# Sheet1.net
KiCad netlist of a schematic drawn in Altium Designer
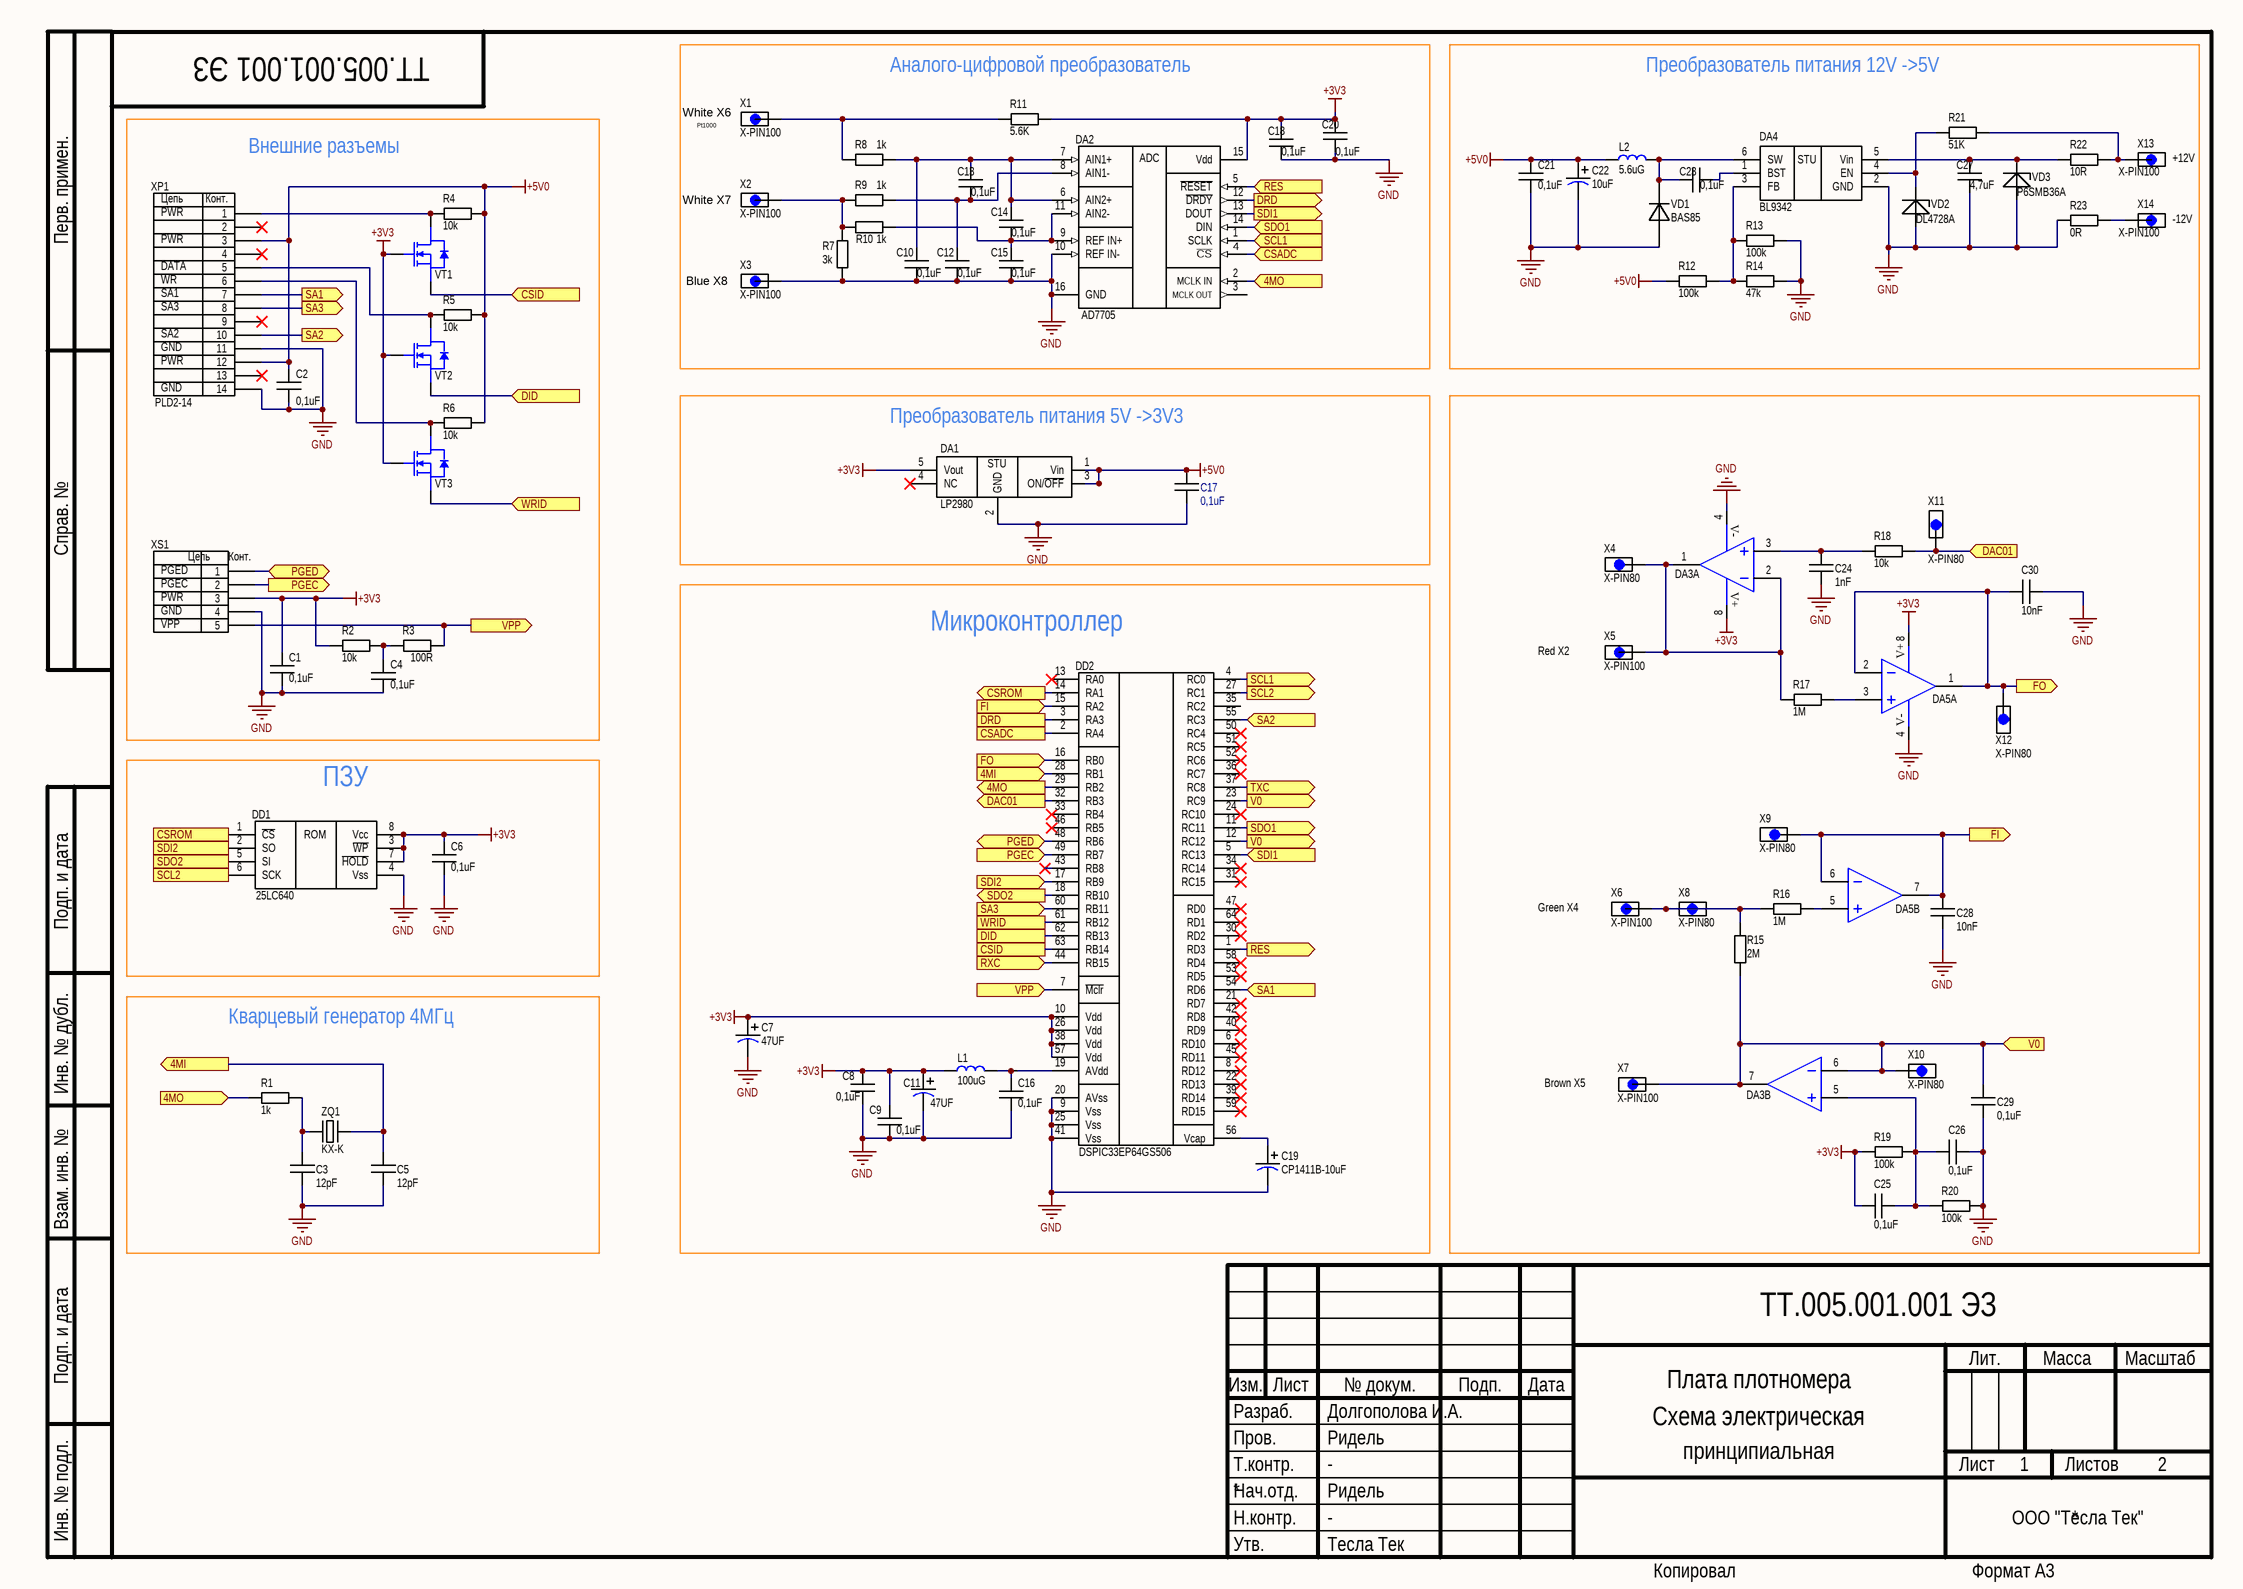
[diagram p0: Sheet1.SCHDOC]

(export (version "E")
  (design (tool "Eeschema 10.0.6"))
  (components
    (comp (ref "C1")
      (value "0,1uF")
      (footprint "0805C")
      (description "C0805 0,1uF")
      (fields
        (field (name "PART NUMBER") "SMD CAP CER 0.1uF ±10% 25V X7R 0805")
        (field (name "ADDED_BY") "ridel_av@teslatec.ru")
      )
      (libsource (lib "81801_1") (part "C0805-0,1uF"))
    )
    (comp (ref "C2")
      (value "0,1uF")
      (footprint "0805C")
      (description "C0805 0,1uF")
      (fields
        (field (name "PART NUMBER") "SMD CAP CER 0.1uF ±10% 25V X7R 0805")
        (field (name "ADDED_BY") "ridel_av@teslatec.ru")
      )
      (libsource (lib "81801_1") (part "C0805-0,1uF"))
    )
    (comp (ref "C3")
      (value "12pF")
      (footprint "0805C")
      (description "C0805 12pF")
      (fields
        (field (name "PART NUMBER") "SMD CAP CER 12pF ±10% 10V X7R 0805")
        (field (name "ADDED_BY") "ridel_av@teslatec.ru")
      )
      (libsource (lib "81801_1") (part "C0805-12pF"))
    )
    (comp (ref "C4")
      (value "0,1uF")
      (footprint "0805C")
      (description "C0805 0,1uF")
      (fields
        (field (name "PART NUMBER") "SMD CAP CER 0.1uF ±10% 25V X7R 0805")
        (field (name "ADDED_BY") "ridel_av@teslatec.ru")
      )
      (libsource (lib "81801_1") (part "C0805-0,1uF"))
    )
    (comp (ref "C5")
      (value "12pF")
      (footprint "0805C")
      (description "C0805 12pF")
      (fields
        (field (name "PART NUMBER") "SMD CAP CER 12pF ±10% 10V X7R 0805")
        (field (name "ADDED_BY") "ridel_av@teslatec.ru")
      )
      (libsource (lib "81801_1") (part "C0805-12pF"))
    )
    (comp (ref "C6")
      (value "0,1uF")
      (footprint "0805C")
      (description "C0805 0,1uF")
      (fields
        (field (name "PART NUMBER") "SMD CAP CER 0.1uF ±10% 25V X7R 0805")
        (field (name "ADDED_BY") "ridel_av@teslatec.ru")
      )
      (libsource (lib "81801_1") (part "C0805-0,1uF"))
    )
    (comp (ref "C7")
      (value "47UF")
      (footprint "B1411_3528")
      (description "CP1411B 47UF 6V3")
      (fields
        (field (name "PART NUMBER") "SMD CAP TANTAL 47uF ±10% 6V3 1411B")
        (field (name "ADDED_BY") "ridel_av@teslatec.ru")
      )
      (libsource (lib "81801_1") (part "CP1411B-47UF"))
    )
    (comp (ref "C8")
      (value "0,1uF")
      (footprint "0805C")
      (description "C0805 0,1uF")
      (fields
        (field (name "PART NUMBER") "SMD CAP CER 0.1uF ±10% 25V X7R 0805")
        (field (name "ADDED_BY") "ridel_av@teslatec.ru")
      )
      (libsource (lib "81801_1") (part "C0805-0,1uF"))
    )
    (comp (ref "C9")
      (value "0,1uF")
      (footprint "0805C")
      (description "C0805 0,1uF")
      (fields
        (field (name "PART NUMBER") "SMD CAP CER 0.1uF ±10% 25V X7R 0805")
        (field (name "ADDED_BY") "ridel_av@teslatec.ru")
      )
      (libsource (lib "81801_1") (part "C0805-0,1uF"))
    )
    (comp (ref "C10")
      (value "0,1uF")
      (footprint "0805C")
      (description "C0805 0,1uF")
      (fields
        (field (name "PART NUMBER") "SMD CAP CER 0.1uF ±10% 25V X7R 0805")
        (field (name "ADDED_BY") "ridel_av@teslatec.ru")
      )
      (libsource (lib "81801_1") (part "C0805-0,1uF"))
    )
    (comp (ref "C11")
      (value "47UF")
      (footprint "B1411_3528")
      (description "CP1411B 47UF 6V3")
      (fields
        (field (name "PART NUMBER") "SMD CAP TANTAL 47uF ±10% 6V3 1411B")
        (field (name "ADDED_BY") "ridel_av@teslatec.ru")
      )
      (libsource (lib "81801_1") (part "CP1411B-47UF"))
    )
    (comp (ref "C12")
      (value "0,1uF")
      (footprint "0805C")
      (description "C0805 0,1uF")
      (fields
        (field (name "PART NUMBER") "SMD CAP CER 0.1uF ±10% 25V X7R 0805")
        (field (name "ADDED_BY") "ridel_av@teslatec.ru")
      )
      (libsource (lib "81801_1") (part "C0805-0,1uF"))
    )
    (comp (ref "C13")
      (value "0,1uF")
      (footprint "0805C")
      (description "C0805 0,1uF")
      (fields
        (field (name "PART NUMBER") "SMD CAP CER 0.1uF ±10% 25V X7R 0805")
        (field (name "ADDED_BY") "ridel_av@teslatec.ru")
      )
      (libsource (lib "81801_1") (part "C0805-0,1uF"))
    )
    (comp (ref "C14")
      (value "0,1uF")
      (footprint "0805C")
      (description "C0805 0,1uF")
      (fields
        (field (name "PART NUMBER") "SMD CAP CER 0.1uF ±10% 25V X7R 0805")
        (field (name "ADDED_BY") "ridel_av@teslatec.ru")
      )
      (libsource (lib "81801_1") (part "C0805-0,1uF"))
    )
    (comp (ref "C15")
      (value "0,1uF")
      (footprint "0805C")
      (description "C0805 0,1uF")
      (fields
        (field (name "PART NUMBER") "SMD CAP CER 0.1uF ±10% 25V X7R 0805")
        (field (name "ADDED_BY") "ridel_av@teslatec.ru")
      )
      (libsource (lib "81801_1") (part "C0805-0,1uF"))
    )
    (comp (ref "C16")
      (value "0,1uF")
      (footprint "0805C")
      (description "C0805 0,1uF")
      (fields
        (field (name "PART NUMBER") "SMD CAP CER 0.1uF ±10% 25V X7R 0805")
        (field (name "ADDED_BY") "ridel_av@teslatec.ru")
      )
      (libsource (lib "81801_1") (part "C0805-0,1uF"))
    )
    (comp (ref "C17")
      (value "0,1uF")
      (footprint "0805C")
      (description "C0805 0,1uF")
      (fields
        (field (name "PART NUMBER") "SMD CAP CER 0.1uF ±10% 25V X7R 0805")
        (field (name "ADDED_BY") "ridel_av@teslatec.ru")
      )
      (libsource (lib "81801_1") (part "C0805-0,1uF"))
    )
    (comp (ref "C18")
      (value "0,1uF")
      (footprint "0805C")
      (description "C0805 0,1uF")
      (fields
        (field (name "PART NUMBER") "SMD CAP CER 0.1uF ±10% 25V X7R 0805")
        (field (name "ADDED_BY") "ridel_av@teslatec.ru")
      )
      (libsource (lib "81801_1") (part "C0805-0,1uF"))
    )
    (comp (ref "C19")
      (value "CP1411B-10uF")
      (footprint "B1411_3528")
      (description "CP1411B 10uF 6V3")
      (fields
        (field (name "PART NUMBER") "SMD CAP TANTAL 10uF ±10% 6V3 1411B")
        (field (name "ADDED_BY") "ridel_av@teslatec.ru")
      )
      (libsource (lib "81801_1") (part "CP1411B-10uF"))
    )
    (comp (ref "C20")
      (value "0,1uF")
      (footprint "0805C")
      (description "C0805 0,1uF")
      (fields
        (field (name "PART NUMBER") "SMD CAP CER 0.1uF ±10% 25V X7R 0805")
        (field (name "ADDED_BY") "ridel_av@teslatec.ru")
      )
      (libsource (lib "81801_1") (part "C0805-0,1uF"))
    )
    (comp (ref "C21")
      (value "0,1uF")
      (footprint "0805C")
      (description "C0805 0,1uF")
      (fields
        (field (name "PART NUMBER") "SMD CAP CER 0.1uF ±10% 25V X7R 0805")
        (field (name "ADDED_BY") "ridel_av@teslatec.ru")
      )
      (libsource (lib "81801_1") (part "C0805-0,1uF"))
    )
    (comp (ref "C22")
      (value "10uF")
      (footprint "B1411_3528")
      (description "CP1411B 10uF 10V")
      (fields
        (field (name "PART NUMBER") "SMD CAP TANTAL 10uF ±10% 10V 1411B")
        (field (name "ADDED_BY") "ridel_av@teslatec.ru")
      )
      (libsource (lib "81801_1") (part "CP1411B-10uF-10V"))
    )
    (comp (ref "C23")
      (value "0,1uF")
      (footprint "0805C")
      (description "C0805 0,1uF")
      (fields
        (field (name "PART NUMBER") "SMD CAP CER 0.1uF ±10% 25V X7R 0805")
        (field (name "ADDED_BY") "ridel_av@teslatec.ru")
      )
      (libsource (lib "81801_1") (part "C0805-0,1uF"))
    )
    (comp (ref "C24")
      (value "1nF")
      (footprint "0805C")
      (description "C0805 1nF")
      (fields
        (field (name "PART NUMBER") "SMD CAP CER 1nF ±10% 50V X7R 0805")
        (field (name "ADDED_BY") "ridel_av@teslatec.ru")
      )
      (libsource (lib "81801_1") (part "C0805-1nF"))
    )
    (comp (ref "C25")
      (value "0,1uF")
      (footprint "0805C")
      (description "C0805 0,1uF")
      (fields
        (field (name "PART NUMBER") "SMD CAP CER 0.1uF ±10% 25V X7R 0805")
        (field (name "ADDED_BY") "ridel_av@teslatec.ru")
      )
      (libsource (lib "81801_1") (part "C0805-0,1uF"))
    )
    (comp (ref "C26")
      (value "0,1uF")
      (footprint "0805C")
      (description "C0805 0,1uF")
      (fields
        (field (name "PART NUMBER") "SMD CAP CER 0.1uF ±10% 25V X7R 0805")
        (field (name "ADDED_BY") "ridel_av@teslatec.ru")
      )
      (libsource (lib "81801_1") (part "C0805-0,1uF"))
    )
    (comp (ref "C27")
      (value "4,7uF")
      (footprint "0805C")
      (description "C0805 4,7uF 50V")
      (fields
        (field (name "PART NUMBER") "SMD CAP CER 4.7uF ±10% 50V X7R 0805")
        (field (name "ADDED_BY") "ridel_av@teslatec.ru")
      )
      (libsource (lib "81801_1") (part "C0805-4,7uF"))
    )
    (comp (ref "C28")
      (value "10nF")
      (footprint "0805C")
      (description "C0805 10nF")
      (fields
        (field (name "PART NUMBER") "SMD CAP CER 10nF ±10% 50V X7R 0805")
        (field (name "ADDED_BY") "ridel_av@teslatec.ru")
      )
      (libsource (lib "81801_1") (part "C0805-10nF"))
    )
    (comp (ref "C29")
      (value "0,1uF")
      (footprint "0805C")
      (description "C0805 0,1uF")
      (fields
        (field (name "PART NUMBER") "SMD CAP CER 0.1uF ±10% 25V X7R 0805")
        (field (name "ADDED_BY") "ridel_av@teslatec.ru")
      )
      (libsource (lib "81801_1") (part "C0805-0,1uF"))
    )
    (comp (ref "C30")
      (value "10nF")
      (footprint "0805C")
      (description "C0805 10nF")
      (fields
        (field (name "PART NUMBER") "SMD CAP CER 10nF ±10% 50V X7R 0805")
        (field (name "ADDED_BY") "ridel_av@teslatec.ru")
      )
      (libsource (lib "81801_1") (part "C0805-10nF"))
    )
    (comp (ref "DA1")
      (value "LP2980")
      (footprint "SOT23-5")
      (description "DA-STU-LP2980, 3.3V, 50mA")
      (fields
        (field (name "PART NUMBER") "LP2980IM5X-3.3/NOPB")
        (field (name "ADDED_BY") "ridel_av@teslatec.ru")
      )
      (libsource (lib "81801_1") (part "DA-STU-LP2980"))
    )
    (comp (ref "DA2")
      (value "AD7705")
      (footprint "SOIC-16")
      (description "DA-ADC-AD7705")
      (fields (field (name "PART NUMBER") "AD7705BR") (field (name "ADDED_BY") "ridel_av@teslatec.ru"))
      (libsource (lib "81801_1") (part "DA-ADC-AD7705SO"))
    )
    (comp (ref "DA3")
      (value "TP6002-SR")
      (footprint "SOIC-8")
      (description "100 mA Output Single-Supply Amplifier")
      (fields (field (name "ADDED_BY") "ridel_av@teslatec.ru"))
      (libsource (lib "81801_1") (part "TP6002-SR"))
    )
    (comp (ref "DA4")
      (value "BL9342")
      (footprint "SOT23-6")
      (description "STU-BL9342, 40V, 600mA")
      (fields (field (name "ADDED_BY") "ridel_av@teslatec.ru"))
      (libsource (lib "81801_1") (part "BL9342"))
    )
    (comp (ref "DA5")
      (value "TP6002-SR")
      (footprint "SOIC-8")
      (description "100 mA Output Single-Supply Amplifier")
      (fields (field (name "ADDED_BY") "ridel_av@teslatec.ru"))
      (libsource (lib "81801_1") (part "TP6002-SR"))
    )
    (comp (ref "DD1")
      (value "25LC640")
      (footprint "SOIC-8")
      (description "25LC640-E/SN, EEPROM, 64Kbit, 2MHz, SPI")
      (fields (field (name "PART NUMBER") "25LC640-E/SN") (field (name "ADDED_BY") "ridel_av@teslatec.ru"))
      (libsource (lib "81801_1") (part "25LC640"))
    )
    (comp (ref "DD2")
      (value "DSPIC33EP64GS506")
      (footprint "TQFP-64")
      (description "DD-CPU-DSPIC33EP64GS506")
      (fields (field (name "ADDED_BY") "ridel_av@teslatec.ru"))
      (libsource (lib "81801_1") (part "DD-CPU-DSPIC33EPXXGS506"))
    )
    (comp (ref "L1")
      (value "100uG")
      (footprint "L1206")
      (description "LQH31CN101K03L, 100 uG, 1206, 10%")
      (fields (field (name "PART NUMBER") "LQH31CN101K03L") (field (name "ADDED_BY") "ridel_av@teslatec.ru"))
      (libsource (lib "81801_1") (part "L1206-100uG"))
    )
    (comp (ref "L2")
      (value "5.6uG")
      (footprint "L1210")
      (description "LQH32MN5R6K23L, 5.6uG, 1210, 10%")
      (fields (field (name "PART NUMBER") "LQH32MN5R6K23L") (field (name "ADDED_BY") "ridel_av@teslatec.ru"))
      (libsource (lib "81801_1") (part "L1210-5.6uG"))
    )
    (comp (ref "R1")
      (value "1k")
      (footprint "R1206")
      (description "R1206 SMD 1k OHM 1% ±100ppm/°C")
      (fields
        (field (name "PART NUMBER") "SMD RES 1k OHM 1% ±100ppm/°C 1206")
        (field (name "ADDED_BY") "ridel_av@teslatec.ru")
      )
      (libsource (lib "81801_1") (part "R1206-1k"))
    )
    (comp (ref "R2")
      (value "10k")
      (footprint "R0805")
      (description "R0805 SMD 10k OHM 1% ±100ppm/°C")
      (fields
        (field (name "PART NUMBER") "SMD RES 10k OHM 1% ±100ppm/°C 0805")
        (field (name "ADDED_BY") "ridel_av@teslatec.ru")
      )
      (libsource (lib "81801_1") (part "R0805-10k"))
    )
    (comp (ref "R3")
      (value "100R")
      (footprint "R1206")
      (description "R1206 100 OHM 1% ±100ppm/°C")
      (fields
        (field (name "PART NUMBER") "SMD RES 100 OHM 1% ±100ppm/°C 1206")
        (field (name "ADDED_BY") "ridel_av@teslatec.ru")
      )
      (libsource (lib "81801_1") (part "R1206-100R"))
    )
    (comp (ref "R4")
      (value "10k")
      (footprint "R0805")
      (description "R0805 SMD 10k OHM 1% ±100ppm/°C")
      (fields
        (field (name "PART NUMBER") "SMD RES 10k OHM 1% ±100ppm/°C 0805")
        (field (name "ADDED_BY") "ridel_av@teslatec.ru")
      )
      (libsource (lib "81801_1") (part "R0805-10k"))
    )
    (comp (ref "R5")
      (value "10k")
      (footprint "R0805")
      (description "R0805 SMD 10k OHM 1% ±100ppm/°C")
      (fields
        (field (name "PART NUMBER") "SMD RES 10k OHM 1% ±100ppm/°C 0805")
        (field (name "ADDED_BY") "ridel_av@teslatec.ru")
      )
      (libsource (lib "81801_1") (part "R0805-10k"))
    )
    (comp (ref "R6")
      (value "10k")
      (footprint "R0805")
      (description "R0805 SMD 10k OHM 1% ±100ppm/°C")
      (fields
        (field (name "PART NUMBER") "SMD RES 10k OHM 1% ±100ppm/°C 0805")
        (field (name "ADDED_BY") "ridel_av@teslatec.ru")
      )
      (libsource (lib "81801_1") (part "R0805-10k"))
    )
    (comp (ref "R7")
      (value "3k")
      (footprint "R1206")
      (description "R1206 SMD 3k OHM 1% ±100ppm/°C")
      (fields
        (field (name "PART NUMBER") "SMD RES 1k OHM 1% ±100ppm/°C 1206")
        (field (name "ADDED_BY") "ridel_av@teslatec.ru")
      )
      (libsource (lib "81801_1") (part "R1206-3k"))
    )
    (comp (ref "R8")
      (value "1k")
      (footprint "R1206")
      (description "R1206 SMD 1k OHM 1% ±100ppm/°C")
      (fields
        (field (name "PART NUMBER") "SMD RES 1k OHM 1% ±100ppm/°C 1206")
        (field (name "ADDED_BY") "ridel_av@teslatec.ru")
      )
      (libsource (lib "81801_1") (part "R1206-1k"))
    )
    (comp (ref "R9")
      (value "1k")
      (footprint "R1206")
      (description "R1206 SMD 1k OHM 1% ±100ppm/°C")
      (fields
        (field (name "PART NUMBER") "SMD RES 1k OHM 1% ±100ppm/°C 1206")
        (field (name "ADDED_BY") "ridel_av@teslatec.ru")
      )
      (libsource (lib "81801_1") (part "R1206-1k"))
    )
    (comp (ref "R10")
      (value "1k")
      (footprint "R1206")
      (description "R1206 SMD 1k OHM 1% ±100ppm/°C")
      (fields
        (field (name "PART NUMBER") "SMD RES 1k OHM 1% ±100ppm/°C 1206")
        (field (name "ADDED_BY") "ridel_av@teslatec.ru")
      )
      (libsource (lib "81801_1") (part "R1206-1k"))
    )
    (comp (ref "R11")
      (value "5.6K")
      (footprint "R1206")
      (description "R1206 5.6k OHM 1% ±100ppm/°C")
      (fields
        (field (name "PART NUMBER") "SMD RES 5.6k OHM 1% ±100ppm/°C 1206")
        (field (name "ADDED_BY") "ridel_av@teslatec.ru")
      )
      (libsource (lib "81801_1") (part "R1206-5.6K"))
    )
    (comp (ref "R12")
      (value "100k")
      (footprint "R1206")
      (description "R1206 100k OHM 1% ±100ppm/°C")
      (fields
        (field (name "PART NUMBER") "SMD RES 100k OHM 1% ±100ppm/°C 1206")
        (field (name "ADDED_BY") "ridel_av@teslatec.ru")
      )
      (libsource (lib "81801_1") (part "R1206-100k"))
    )
    (comp (ref "R13")
      (value "100k")
      (footprint "R1206")
      (description "R1206 100k OHM 1% ±100ppm/°C")
      (fields
        (field (name "PART NUMBER") "SMD RES 100k OHM 1% ±100ppm/°C 1206")
        (field (name "ADDED_BY") "ridel_av@teslatec.ru")
      )
      (libsource (lib "81801_1") (part "R1206-100k"))
    )
    (comp (ref "R14")
      (value "47k")
      (footprint "R1206")
      (description "R1206 47k OHM 1% ±100ppm/°C")
      (fields
        (field (name "PART NUMBER") "SMD RES 47k OHM 1% ±100ppm/°C 1206")
        (field (name "ADDED_BY") "ridel_av@teslatec.ru")
      )
      (libsource (lib "81801_1") (part "R1206-47k"))
    )
    (comp (ref "R15")
      (value "2M")
      (footprint "R1206")
      (description "R1206 2M OHM 1% ±100ppm/°C")
      (fields
        (field (name "PART NUMBER") "SMD RES 2M OHM 1% ±100ppm/°C 1206")
        (field (name "ADDED_BY") "ridel_av@teslatec.ru")
      )
      (libsource (lib "81801_1") (part "R1206-2M"))
    )
    (comp (ref "R16")
      (value "1M")
      (footprint "R1206")
      (description "R1206 1M OHM 1% ±100ppm/°C")
      (fields
        (field (name "PART NUMBER") "SMD RES 1M OHM 1% ±100ppm/°C 1206")
        (field (name "ADDED_BY") "ridel_av@teslatec.ru")
      )
      (libsource (lib "81801_1") (part "R1206-1M"))
    )
    (comp (ref "R17")
      (value "1M")
      (footprint "R1206")
      (description "R1206 1M OHM 1% ±100ppm/°C")
      (fields
        (field (name "PART NUMBER") "SMD RES 1M OHM 1% ±100ppm/°C 1206")
        (field (name "ADDED_BY") "ridel_av@teslatec.ru")
      )
      (libsource (lib "81801_1") (part "R1206-1M"))
    )
    (comp (ref "R18")
      (value "10k")
      (footprint "R0805")
      (description "R0805 SMD 10k OHM 1% ±100ppm/°C")
      (fields
        (field (name "PART NUMBER") "SMD RES 10k OHM 1% ±100ppm/°C 0805")
        (field (name "ADDED_BY") "ridel_av@teslatec.ru")
      )
      (libsource (lib "81801_1") (part "R0805-10k"))
    )
    (comp (ref "R19")
      (value "100k")
      (footprint "R1206")
      (description "R1206 100k OHM 1% ±100ppm/°C")
      (fields
        (field (name "PART NUMBER") "SMD RES 100k OHM 1% ±100ppm/°C 1206")
        (field (name "ADDED_BY") "ridel_av@teslatec.ru")
      )
      (libsource (lib "81801_1") (part "R1206-100k"))
    )
    (comp (ref "R20")
      (value "100k")
      (footprint "R1206")
      (description "R1206 100k OHM 1% ±100ppm/°C")
      (fields
        (field (name "PART NUMBER") "SMD RES 100k OHM 1% ±100ppm/°C 1206")
        (field (name "ADDED_BY") "ridel_av@teslatec.ru")
      )
      (libsource (lib "81801_1") (part "R1206-100k"))
    )
    (comp (ref "R21")
      (value "51K")
      (footprint "R1206")
      (description "R1206 51K OHM 1% ±100ppm/°C")
      (fields
        (field (name "PART NUMBER") "SMD RES 51K OHM 1% ±100ppm/°C 1206")
        (field (name "ADDED_BY") "ridel_av@teslatec.ru")
      )
      (libsource (lib "81801_1") (part "R1206-51K"))
    )
    (comp (ref "R22")
      (value "10R")
      (footprint "R1206")
      (description "R1206 10 OHM 1% ±100ppm/°C")
      (fields
        (field (name "PART NUMBER") "SMD RES 10 OHM 1% ±100ppm/°C 1206")
        (field (name "ADDED_BY") "ridel_av@teslatec.ru")
      )
      (libsource (lib "81801_1") (part "R1206-10R"))
    )
    (comp (ref "R23")
      (value "0R")
      (footprint "R1206")
      (description "R1206-0R")
      (fields
        (field (name "PART NUMBER") "SMD RES 0 OHM 1% ±100ppm/°C 1206")
        (field (name "ADDED_BY") "ridel_av@teslatec.ru")
      )
      (libsource (lib "81801_1") (part "R1206-0R"))
    )
    (comp (ref "VD1")
      (value "BAS85")
      (footprint "SOD-80 MiniMELF")
      (description "BAS85 30В 0.2А")
      (fields (field (name "ADDED_BY") "ridel_av@teslatec.ru"))
      (libsource (lib "81801_1") (part "BAS85"))
    )
    (comp (ref "VD2")
      (value "DL4728A")
      (footprint "DO-213AB")
      (description "DL4728A, 3V3")
      (fields (field (name "ADDED_BY") "ridel_av@teslatec.ru"))
      (libsource (lib "81801_1") (part "DL4728A"))
    )
    (comp (ref "VD3")
      (value "P6SMB36A")
      (footprint "SMB(DO-214AA )")
      (description "P6SMB36A, 49.9V")
      (fields (field (name "ADDED_BY") "ridel_av@teslatec.ru"))
      (libsource (lib "81801_1") (part "P6SMB36A"))
    )
    (comp (ref "VT1")
      (value "VT-MOSFET-N-SOT23")
      (footprint "SOT-23-3")
      (description "2N7002, MOSFET-N, 60V, 115mA, SOT-23-3")
      (fields (field (name "PART NUMBER") "2N7002") (field (name "ADDED_BY") "ridel_av@teslatec.ru"))
      (libsource (lib "81801_1") (part "2N7002"))
    )
    (comp (ref "VT2")
      (value "VT-MOSFET-N-SOT23")
      (footprint "SOT-23-3")
      (description "2N7002, MOSFET-N, 60V, 115mA, SOT-23-3")
      (fields (field (name "PART NUMBER") "2N7002") (field (name "ADDED_BY") "ridel_av@teslatec.ru"))
      (libsource (lib "81801_1") (part "2N7002"))
    )
    (comp (ref "VT3")
      (value "VT-MOSFET-N-SOT23")
      (footprint "SOT-23-3")
      (description "2N7002, MOSFET-N, 60V, 115mA, SOT-23-3")
      (fields (field (name "PART NUMBER") "2N7002") (field (name "ADDED_BY") "ridel_av@teslatec.ru"))
      (libsource (lib "81801_1") (part "2N7002"))
    )
    (comp (ref "X1")
      (value "X-PIN100")
      (footprint "Xpin100")
      (fields (field (name "ADDED_BY") "ridel_av@teslatec.ru"))
      (libsource (lib "81801_1") (part "X-PIN100"))
    )
    (comp (ref "X2")
      (value "X-PIN100")
      (footprint "Xpin100")
      (fields (field (name "ADDED_BY") "ridel_av@teslatec.ru"))
      (libsource (lib "81801_1") (part "X-PIN100"))
    )
    (comp (ref "X3")
      (value "X-PIN100")
      (footprint "Xpin100")
      (fields (field (name "ADDED_BY") "ridel_av@teslatec.ru"))
      (libsource (lib "81801_1") (part "X-PIN100"))
    )
    (comp (ref "X4")
      (value "X-PIN80")
      (footprint "Xpin80")
      (fields (field (name "ADDED_BY") "ridel_av@teslatec.ru"))
      (libsource (lib "81801_1") (part "X-PIN80"))
    )
    (comp (ref "X5")
      (value "X-PIN100")
      (footprint "Xpin100")
      (fields (field (name "ADDED_BY") "ridel_av@teslatec.ru"))
      (libsource (lib "81801_1") (part "X-PIN100"))
    )
    (comp (ref "X6")
      (value "X-PIN100")
      (footprint "Xpin100")
      (fields (field (name "ADDED_BY") "ridel_av@teslatec.ru"))
      (libsource (lib "81801_1") (part "X-PIN100"))
    )
    (comp (ref "X7")
      (value "X-PIN100")
      (footprint "Xpin100")
      (fields (field (name "ADDED_BY") "ridel_av@teslatec.ru"))
      (libsource (lib "81801_1") (part "X-PIN100"))
    )
    (comp (ref "X8")
      (value "X-PIN80")
      (footprint "Xpin80")
      (fields (field (name "ADDED_BY") "ridel_av@teslatec.ru"))
      (libsource (lib "81801_1") (part "X-PIN80"))
    )
    (comp (ref "X9")
      (value "X-PIN80")
      (footprint "Xpin80")
      (fields (field (name "ADDED_BY") "ridel_av@teslatec.ru"))
      (libsource (lib "81801_1") (part "X-PIN80"))
    )
    (comp (ref "X10")
      (value "X-PIN80")
      (footprint "Xpin80")
      (fields (field (name "ADDED_BY") "ridel_av@teslatec.ru"))
      (libsource (lib "81801_1") (part "X-PIN80"))
    )
    (comp (ref "X11")
      (value "X-PIN80")
      (footprint "Xpin80")
      (fields (field (name "ADDED_BY") "ridel_av@teslatec.ru"))
      (libsource (lib "81801_1") (part "X-PIN80"))
    )
    (comp (ref "X12")
      (value "X-PIN80")
      (footprint "Xpin80")
      (fields (field (name "ADDED_BY") "ridel_av@teslatec.ru"))
      (libsource (lib "81801_1") (part "X-PIN80"))
    )
    (comp (ref "X13")
      (value "X-PIN100")
      (footprint "Xpin100")
      (fields (field (name "ADDED_BY") "ridel_av@teslatec.ru"))
      (libsource (lib "81801_1") (part "X-PIN100"))
    )
    (comp (ref "X14")
      (value "X-PIN100")
      (footprint "Xpin100")
      (fields (field (name "ADDED_BY") "ridel_av@teslatec.ru"))
      (libsource (lib "81801_1") (part "X-PIN100"))
    )
    (comp (ref "XP1")
      (value "PLD2-14")
      (footprint "PLD-14- 2.0mm")
      (fields
        (field (name "PART NUMBER") "DS1025-05-2X7P8BV1-B")
        (field (name "ADDED_BY") "ridel_av@teslatec.ru")
      )
      (libsource (lib "81801_1") (part "PLD2-14"))
    )
    (comp (ref "XS1")
      (value "PBS2-5")
      (footprint "PBS-5")
      (fields (field (name "PART NUMBER") "C6801-05ASGL00R") (field (name "ADDED_BY") "ridel_av@teslatec.ru"))
      (libsource (lib "81801_1") (part "PBS2-5"))
    )
    (comp (ref "ZQ1")
      (value "KX-K")
      (footprint "HC¦49US")
      (description "KX-K 4MHz HC/49US")
      (fields
        (field (name "PART NUMBER") "ABLS-4.000MHZ-K4T")
        (field (name "ADDED_BY") "ridel_av@teslatec.ru")
      )
      (libsource (lib "81801_1") (part "ABLS-4.000MHZ-K4T"))
    )
  )
  (nets
    (net (code "1") (name "+3V3") (class "Default")
      (node (ref "C1") (pin "1") (pinfunction "1_1") (pintype "passive"))
      (node (ref "C11") (pin "1") (pinfunction "1_1") (pintype "passive"))
      (node (ref "C18") (pin "2") (pinfunction "2_2") (pintype "passive"))
      (node (ref "C20") (pin "1") (pinfunction "1_1") (pintype "passive"))
      (node (ref "C25") (pin "1") (pinfunction "1_1") (pintype "passive"))
      (node (ref "C6") (pin "2") (pinfunction "2_2") (pintype "passive"))
      (node (ref "C7") (pin "1") (pinfunction "1_1") (pintype "passive"))
      (node (ref "C8") (pin "1") (pinfunction "1_1") (pintype "passive"))
      (node (ref "C9") (pin "1") (pinfunction "1_1") (pintype "passive"))
      (node (ref "DA1") (pin "5") (pinfunction "Vout_5") (pintype "passive"))
      (node (ref "DA2") (pin "15") (pinfunction "Vdd_15") (pintype "power_in"))
      (node (ref "DA3") (pin "8") (pinfunction "8_8") (pintype "passive"))
      (node (ref "DA5") (pin "8") (pinfunction "8_8") (pintype "passive"))
      (node (ref "DD1") (pin "3") (pinfunction "~{WP}_3") (pintype "passive"))
      (node (ref "DD1") (pin "7") (pinfunction "~{HOLD}_7") (pintype "passive"))
      (node (ref "DD1") (pin "8") (pinfunction "Vcc_8") (pintype "passive"))
      (node (ref "DD2") (pin "10") (pinfunction "Vdd_10") (pintype "passive"))
      (node (ref "DD2") (pin "26") (pinfunction "Vdd_26") (pintype "passive"))
      (node (ref "DD2") (pin "38") (pinfunction "Vdd_38") (pintype "passive"))
      (node (ref "DD2") (pin "57") (pinfunction "Vdd_57") (pintype "passive"))
      (node (ref "L1") (pin "1") (pinfunction "1_1") (pintype "passive"))
      (node (ref "R11") (pin "2") (pinfunction "2_2") (pintype "passive"))
      (node (ref "R19") (pin "1") (pinfunction "1_1") (pintype "passive"))
      (node (ref "R2") (pin "1") (pinfunction "1_1") (pintype "passive"))
      (node (ref "VT1") (pin "1") (pinfunction "1_1") (pintype "passive"))
      (node (ref "VT2") (pin "1") (pinfunction "1_1") (pintype "passive"))
      (node (ref "VT3") (pin "1") (pinfunction "1_1") (pintype "passive"))
      (node (ref "XS1") (pin "3") (pinfunction "3_3") (pintype "passive"))
    )
    (net (code "2") (name "+5V0") (class "Default")
      (node (ref "C17") (pin "1") (pinfunction "1_1") (pintype "passive"))
      (node (ref "C2") (pin "1") (pinfunction "1_1") (pintype "passive"))
      (node (ref "C21") (pin "1") (pinfunction "1_1") (pintype "passive"))
      (node (ref "C22") (pin "1") (pinfunction "1_1") (pintype "passive"))
      (node (ref "DA1") (pin "1") (pinfunction "Vin_1") (pintype "passive"))
      (node (ref "DA1") (pin "3") (pinfunction "ON/~{OFF}_3") (pintype "passive"))
      (node (ref "L2") (pin "1") (pinfunction "1_1") (pintype "passive"))
      (node (ref "R12") (pin "1") (pinfunction "1_1") (pintype "passive"))
      (node (ref "R4") (pin "2") (pinfunction "2_2") (pintype "passive"))
      (node (ref "R5") (pin "2") (pinfunction "2_2") (pintype "passive"))
      (node (ref "R6") (pin "2") (pinfunction "2_2") (pintype "passive"))
      (node (ref "XP1") (pin "12") (pinfunction "12_12") (pintype "passive"))
      (node (ref "XP1") (pin "3") (pinfunction "3_3") (pintype "passive"))
    )
    (net (code "3") (name "/4MI") (class "Default")
      (node (ref "C5") (pin "1") (pinfunction "1_1") (pintype "passive"))
      (node (ref "DD2") (pin "28") (pinfunction "RB1_28") (pintype "passive"))
      (node (ref "ZQ1") (pin "2") (pinfunction "OSC2_2") (pintype "passive"))
    )
    (net (code "4") (name "/4MO") (class "Default")
      (node (ref "DA2") (pin "2") (pinfunction "MCLK_IN_2") (pintype "input"))
      (node (ref "DD2") (pin "29") (pinfunction "RB2_29") (pintype "passive"))
      (node (ref "R1") (pin "1") (pinfunction "1_1") (pintype "passive"))
    )
    (net (code "5") (name "/CSADC") (class "Default")
      (node (ref "DA2") (pin "4") (pinfunction "~{CS}_4") (pintype "input"))
      (node (ref "DD2") (pin "2") (pinfunction "RA4_2") (pintype "passive"))
    )
    (net (code "6") (name "/CSID") (class "Default")
      (node (ref "DD2") (pin "63") (pinfunction "RB14_63") (pintype "passive"))
      (node (ref "VT1") (pin "2") (pinfunction "2_2") (pintype "passive"))
    )
    (net (code "7") (name "/CSROM") (class "Default")
      (node (ref "DD1") (pin "1") (pinfunction "~{CS}_1") (pintype "passive"))
      (node (ref "DD2") (pin "14") (pinfunction "RA1_14") (pintype "passive"))
    )
    (net (code "8") (name "/DAC01") (class "Default")
      (node (ref "DD2") (pin "32") (pinfunction "RB3_32") (pintype "passive"))
      (node (ref "R18") (pin "2") (pinfunction "2_2") (pintype "passive"))
      (node (ref "X11") (pin "1") (pinfunction "Contact0_1") (pintype "passive"))
    )
    (net (code "9") (name "/DID") (class "Default")
      (node (ref "DD2") (pin "62") (pinfunction "RB13_62") (pintype "passive"))
      (node (ref "VT2") (pin "2") (pinfunction "2_2") (pintype "passive"))
    )
    (net (code "10") (name "/DRD") (class "Default")
      (node (ref "DA2") (pin "12") (pinfunction "~{DRDY}_12") (pintype "output"))
      (node (ref "DD2") (pin "3") (pinfunction "RA3_3") (pintype "passive"))
    )
    (net (code "11") (name "/FI") (class "Default")
      (node (ref "C28") (pin "1") (pinfunction "1_1") (pintype "passive"))
      (node (ref "DA5") (pin "6") (pinfunction "6_6") (pintype "passive"))
      (node (ref "DA5") (pin "7") (pinfunction "7_7") (pintype "passive"))
      (node (ref "DD2") (pin "15") (pinfunction "RA2_15") (pintype "passive"))
      (node (ref "X9") (pin "1") (pinfunction "Contact0_1") (pintype "passive"))
    )
    (net (code "12") (name "/FO") (class "Default")
      (node (ref "C30") (pin "1") (pinfunction "1_1") (pintype "passive"))
      (node (ref "DA5") (pin "1") (pinfunction "1_1") (pintype "passive"))
      (node (ref "DA5") (pin "2") (pinfunction "2_2") (pintype "passive"))
      (node (ref "DD2") (pin "16") (pinfunction "RB0_16") (pintype "passive"))
      (node (ref "X12") (pin "1") (pinfunction "Contact0_1") (pintype "passive"))
    )
    (net (code "13") (name "/PGEC") (class "Default")
      (node (ref "DD2") (pin "49") (pinfunction "RB7_49") (pintype "passive"))
      (node (ref "XS1") (pin "2") (pinfunction "2_2") (pintype "passive"))
    )
    (net (code "14") (name "/PGED") (class "Default")
      (node (ref "DD2") (pin "48") (pinfunction "RB6_48") (pintype "passive"))
      (node (ref "XS1") (pin "1") (pinfunction "1_1") (pintype "passive"))
    )
    (net (code "15") (name "/RES") (class "Default")
      (node (ref "DA2") (pin "5") (pinfunction "~{RESET}_5") (pintype "input"))
      (node (ref "DD2") (pin "1") (pinfunction "RD3_1") (pintype "passive"))
    )
    (net (code "16") (name "/RXC") (class "Default")
      (node (ref "DD2") (pin "44") (pinfunction "RB15_44") (pintype "passive"))
    )
    (net (code "17") (name "/SA1") (class "Default")
      (node (ref "DD2") (pin "54") (pinfunction "RD6_54") (pintype "passive"))
      (node (ref "XP1") (pin "7") (pinfunction "7_7") (pintype "passive"))
    )
    (net (code "18") (name "/SA2") (class "Default")
      (node (ref "DD2") (pin "55") (pinfunction "RC3_55") (pintype "passive"))
      (node (ref "XP1") (pin "10") (pinfunction "10_10") (pintype "passive"))
    )
    (net (code "19") (name "/SA3") (class "Default")
      (node (ref "DD2") (pin "60") (pinfunction "RB11_60") (pintype "passive"))
      (node (ref "XP1") (pin "8") (pinfunction "8_8") (pintype "passive"))
    )
    (net (code "20") (name "/SCL1") (class "Default")
      (node (ref "DA2") (pin "1") (pinfunction "SCLK_1") (pintype "input"))
      (node (ref "DD2") (pin "4") (pinfunction "RC0_4") (pintype "passive"))
    )
    (net (code "21") (name "/SCL2") (class "Default")
      (node (ref "DD1") (pin "6") (pinfunction "SCK_6") (pintype "passive"))
      (node (ref "DD2") (pin "27") (pinfunction "RC1_27") (pintype "passive"))
    )
    (net (code "22") (name "/SDI1") (class "Default")
      (node (ref "DA2") (pin "13") (pinfunction "DOUT_13") (pintype "output"))
      (node (ref "DD2") (pin "5") (pinfunction "RC13_5") (pintype "passive"))
    )
    (net (code "23") (name "/SDI2") (class "Default")
      (node (ref "DD1") (pin "2") (pinfunction "SO_2") (pintype "passive"))
      (node (ref "DD2") (pin "17") (pinfunction "RB9_17") (pintype "passive"))
    )
    (net (code "24") (name "/SDO1") (class "Default")
      (node (ref "DA2") (pin "14") (pinfunction "DIN_14") (pintype "input"))
      (node (ref "DD2") (pin "11") (pinfunction "RC11_11") (pintype "passive"))
    )
    (net (code "25") (name "/SDO2") (class "Default")
      (node (ref "DD1") (pin "5") (pinfunction "SI_5") (pintype "passive"))
      (node (ref "DD2") (pin "18") (pinfunction "RB10_18") (pintype "passive"))
    )
    (net (code "26") (name "/TXC") (class "Default")
      (node (ref "DD2") (pin "37") (pinfunction "RC8_37") (pintype "passive"))
    )
    (net (code "27") (name "/V0") (class "Default")
      (node (ref "C29") (pin "1") (pinfunction "1_1") (pintype "passive"))
      (node (ref "DA3") (pin "6") (pinfunction "6_6") (pintype "passive"))
      (node (ref "DA3") (pin "7") (pinfunction "7_7") (pintype "passive"))
      (node (ref "DD2") (pin "12") (pinfunction "RC12_12") (pintype "passive"))
      (node (ref "DD2") (pin "23") (pinfunction "RC9_23") (pintype "passive"))
      (node (ref "R15") (pin "1") (pinfunction "1_1") (pintype "passive"))
      (node (ref "X10") (pin "1") (pinfunction "Contact0_1") (pintype "passive"))
      (node (ref "X7") (pin "1") (pintype "passive"))
    )
    (net (code "28") (name "/VPP") (class "Default")
      (node (ref "DD2") (pin "7") (pinfunction "~{Mclr}_7") (pintype "passive"))
      (node (ref "R3") (pin "2") (pinfunction "2_2") (pintype "passive"))
      (node (ref "XS1") (pin "5") (pinfunction "5_5") (pintype "passive"))
    )
    (net (code "29") (name "/WRID") (class "Default")
      (node (ref "DD2") (pin "61") (pinfunction "RB12_61") (pintype "passive"))
      (node (ref "VT3") (pin "2") (pinfunction "2_2") (pintype "passive"))
    )
    (net (code "30") (name "GND") (class "Default")
      (node (ref "C1") (pin "2") (pinfunction "2_2") (pintype "passive"))
      (node (ref "C10") (pin "2") (pinfunction "2_2") (pintype "passive"))
      (node (ref "C11") (pin "2") (pinfunction "2_2") (pintype "passive"))
      (node (ref "C12") (pin "2") (pinfunction "2_2") (pintype "passive"))
      (node (ref "C15") (pin "2") (pinfunction "2_2") (pintype "passive"))
      (node (ref "C16") (pin "2") (pinfunction "2_2") (pintype "passive"))
      (node (ref "C17") (pin "2") (pinfunction "2_2") (pintype "passive"))
      (node (ref "C18") (pin "1") (pinfunction "1_1") (pintype "passive"))
      (node (ref "C19") (pin "2") (pinfunction "2_2") (pintype "passive"))
      (node (ref "C2") (pin "2") (pinfunction "2_2") (pintype "passive"))
      (node (ref "C20") (pin "2") (pinfunction "2_2") (pintype "passive"))
      (node (ref "C21") (pin "2") (pinfunction "2_2") (pintype "passive"))
      (node (ref "C22") (pin "2") (pinfunction "2_2") (pintype "passive"))
      (node (ref "C24") (pin "1") (pinfunction "1_1") (pintype "passive"))
      (node (ref "C26") (pin "2") (pinfunction "2_2") (pintype "passive"))
      (node (ref "C27") (pin "2") (pinfunction "2_2") (pintype "passive"))
      (node (ref "C28") (pin "2") (pinfunction "2_2") (pintype "passive"))
      (node (ref "C29") (pin "2") (pinfunction "2_2") (pintype "passive"))
      (node (ref "C3") (pin "2") (pinfunction "2_2") (pintype "passive"))
      (node (ref "C30") (pin "2") (pinfunction "2_2") (pintype "passive"))
      (node (ref "C4") (pin "2") (pinfunction "2_2") (pintype "passive"))
      (node (ref "C5") (pin "2") (pinfunction "2_2") (pintype "passive"))
      (node (ref "C6") (pin "1") (pinfunction "1_1") (pintype "passive"))
      (node (ref "C7") (pin "2") (pinfunction "2_2") (pintype "passive"))
      (node (ref "C8") (pin "2") (pinfunction "2_2") (pintype "passive"))
      (node (ref "C9") (pin "2") (pinfunction "2_2") (pintype "passive"))
      (node (ref "DA1") (pin "2") (pinfunction "GND_2") (pintype "passive"))
      (node (ref "DA2") (pin "10") (pinfunction "REF_IN-_10") (pintype "input"))
      (node (ref "DA2") (pin "16") (pinfunction "GND_16") (pintype "power_in"))
      (node (ref "DA3") (pin "4") (pinfunction "4_4") (pintype "passive"))
      (node (ref "DA4") (pin "2") (pinfunction "GND_2") (pintype "passive"))
      (node (ref "DA5") (pin "4") (pinfunction "4_4") (pintype "passive"))
      (node (ref "DD1") (pin "4") (pinfunction "Vss_4") (pintype "passive"))
      (node (ref "DD2") (pin "20") (pinfunction "AVss_20") (pintype "passive"))
      (node (ref "DD2") (pin "25") (pinfunction "Vss_25") (pintype "passive"))
      (node (ref "DD2") (pin "41") (pinfunction "Vss_41") (pintype "passive"))
      (node (ref "DD2") (pin "9") (pinfunction "Vss_9") (pintype "passive"))
      (node (ref "R13") (pin "2") (pinfunction "2_2") (pintype "passive"))
      (node (ref "R14") (pin "2") (pinfunction "2_2") (pintype "passive"))
      (node (ref "R20") (pin "1") (pinfunction "1_1") (pintype "passive"))
      (node (ref "R23") (pin "1") (pinfunction "1_1") (pintype "passive"))
      (node (ref "R7") (pin "1") (pinfunction "1_1") (pintype "passive"))
      (node (ref "VD1") (pin "1") (pinfunction "A_1") (pintype "passive"))
      (node (ref "VD2") (pin "1") (pinfunction "A_1") (pintype "passive"))
      (node (ref "VD3") (pin "1") (pinfunction "A_1") (pintype "passive"))
      (node (ref "X3") (pin "1") (pintype "passive"))
      (node (ref "XP1") (pin "11") (pinfunction "11_11") (pintype "passive"))
      (node (ref "XP1") (pin "14") (pinfunction "14_14") (pintype "passive"))
      (node (ref "XS1") (pin "4") (pinfunction "4_4") (pintype "passive"))
    )
    (net (code "31") (name "Net-(C4-Pad1)") (class "Default")
      (node (ref "C4") (pin "1") (pinfunction "1_1") (pintype "passive"))
      (node (ref "R2") (pin "2") (pinfunction "2_2") (pintype "passive"))
      (node (ref "R3") (pin "1") (pinfunction "1_1") (pintype "passive"))
    )
    (net (code "32") (name "Net-(C24-Pad2)") (class "Default")
      (node (ref "C24") (pin "2") (pinfunction "2_2") (pintype "passive"))
      (node (ref "DA3") (pin "3") (pinfunction "3_3") (pintype "passive"))
      (node (ref "R18") (pin "1") (pinfunction "1_1") (pintype "passive"))
    )
    (net (code "33") (name "Net-(C25-Pad2)") (class "Default")
      (node (ref "C25") (pin "2") (pinfunction "2_2") (pintype "passive"))
      (node (ref "C26") (pin "1") (pinfunction "1_1") (pintype "passive"))
      (node (ref "DA3") (pin "5") (pinfunction "5_5") (pintype "passive"))
      (node (ref "R19") (pin "2") (pinfunction "2_2") (pintype "passive"))
      (node (ref "R20") (pin "2") (pinfunction "2_2") (pintype "passive"))
    )
    (net (code "34") (name "Net-(DA2-AIN1+)") (class "Default")
      (node (ref "C10") (pin "1") (pinfunction "1_1") (pintype "passive"))
      (node (ref "C13") (pin "1") (pinfunction "1_1") (pintype "passive"))
      (node (ref "C14") (pin "1") (pinfunction "1_1") (pintype "passive"))
      (node (ref "DA2") (pin "6") (pinfunction "AIN2+_6") (pintype "input"))
      (node (ref "DA2") (pin "7") (pinfunction "AIN1+_7") (pintype "input"))
      (node (ref "R8") (pin "2") (pinfunction "2_2") (pintype "passive"))
    )
    (net (code "35") (name "Net-(DA2-AIN1-)") (class "Default")
      (node (ref "C12") (pin "1") (pinfunction "1_1") (pintype "passive"))
      (node (ref "C13") (pin "2") (pinfunction "2_2") (pintype "passive"))
      (node (ref "DA2") (pin "8") (pinfunction "AIN1-_8") (pintype "input"))
      (node (ref "R9") (pin "2") (pinfunction "2_2") (pintype "passive"))
    )
    (net (code "36") (name "Net-(DA2-AIN2-)") (class "Default")
      (node (ref "C14") (pin "2") (pinfunction "2_2") (pintype "passive"))
      (node (ref "C15") (pin "1") (pinfunction "1_1") (pintype "passive"))
      (node (ref "DA2") (pin "11") (pinfunction "AIN2-_11") (pintype "input"))
      (node (ref "DA2") (pin "9") (pinfunction "REF_IN+_9") (pintype "input"))
      (node (ref "R10") (pin "2") (pinfunction "2_2") (pintype "passive"))
    )
    (net (code "37") (name "Net-(DA4-BST)") (class "Default")
      (node (ref "C23") (pin "2") (pinfunction "2_2") (pintype "passive"))
      (node (ref "DA4") (pin "1") (pinfunction "BST_1") (pintype "passive"))
    )
    (net (code "38") (name "Net-(DA4-EN)") (class "Default")
      (node (ref "DA4") (pin "4") (pinfunction "EN_4") (pintype "passive"))
      (node (ref "R21") (pin "2") (pinfunction "2_2") (pintype "passive"))
      (node (ref "VD2") (pin "2") (pinfunction "K_2") (pintype "passive"))
    )
    (net (code "39") (name "Net-(DA4-FB)") (class "Default")
      (node (ref "DA4") (pin "3") (pinfunction "FB_3") (pintype "passive"))
      (node (ref "R12") (pin "2") (pinfunction "2_2") (pintype "passive"))
      (node (ref "R13") (pin "1") (pinfunction "1_1") (pintype "passive"))
      (node (ref "R14") (pin "1") (pinfunction "1_1") (pintype "passive"))
    )
    (net (code "40") (name "Net-(DA4-SW)") (class "Default")
      (node (ref "C23") (pin "1") (pinfunction "1_1") (pintype "passive"))
      (node (ref "DA4") (pin "6") (pinfunction "SW_6") (pintype "passive"))
      (node (ref "L2") (pin "2") (pinfunction "2_2") (pintype "passive"))
      (node (ref "VD1") (pin "2") (pinfunction "K_2") (pintype "passive"))
    )
    (net (code "41") (name "Net-(DA4-Vin)") (class "Default")
      (node (ref "C27") (pin "1") (pinfunction "1_1") (pintype "passive"))
      (node (ref "DA4") (pin "5") (pinfunction "Vin_5") (pintype "passive"))
      (node (ref "R22") (pin "1") (pinfunction "1_1") (pintype "passive"))
      (node (ref "VD3") (pin "2") (pinfunction "K_2") (pintype "passive"))
    )
    (net (code "42") (name "Net-(DA5-Pad3)") (class "Default")
      (node (ref "DA5") (pin "3") (pinfunction "3_3") (pintype "passive"))
      (node (ref "R17") (pin "2") (pinfunction "2_2") (pintype "passive"))
    )
    (net (code "43") (name "Net-(DA5-Pad5)") (class "Default")
      (node (ref "DA5") (pin "5") (pinfunction "5_5") (pintype "passive"))
      (node (ref "R16") (pin "2") (pinfunction "2_2") (pintype "passive"))
    )
    (net (code "44") (name "Net-(DD2-AVdd)") (class "Default")
      (node (ref "C16") (pin "1") (pinfunction "1_1") (pintype "passive"))
      (node (ref "DD2") (pin "19") (pinfunction "AVdd_19") (pintype "passive"))
      (node (ref "L1") (pin "2") (pinfunction "2_2") (pintype "passive"))
    )
    (net (code "45") (name "Net-(DD2-Vcap)") (class "Default")
      (node (ref "C19") (pin "1") (pinfunction "1_1") (pintype "passive"))
      (node (ref "DD2") (pin "56") (pinfunction "Vcap_56") (pintype "passive"))
    )
    (net (code "46") (name "Net-(R4-Pad1)") (class "Default")
      (node (ref "R4") (pin "1") (pinfunction "1_1") (pintype "passive"))
      (node (ref "VT1") (pin "3") (pinfunction "3_3") (pintype "passive"))
      (node (ref "VT1") (pin "6") (pinfunction "6_6") (pintype "passive"))
      (node (ref "XP1") (pin "1") (pinfunction "1_1") (pintype "passive"))
    )
    (net (code "47") (name "Net-(R5-Pad1)") (class "Default")
      (node (ref "R5") (pin "1") (pinfunction "1_1") (pintype "passive"))
      (node (ref "VT2") (pin "3") (pinfunction "3_3") (pintype "passive"))
      (node (ref "VT2") (pin "6") (pinfunction "6_6") (pintype "passive"))
      (node (ref "XP1") (pin "5") (pinfunction "5_5") (pintype "passive"))
    )
    (net (code "48") (name "Net-(R6-Pad1)") (class "Default")
      (node (ref "R6") (pin "1") (pinfunction "1_1") (pintype "passive"))
      (node (ref "VT3") (pin "3") (pinfunction "3_3") (pintype "passive"))
      (node (ref "VT3") (pin "6") (pinfunction "6_6") (pintype "passive"))
      (node (ref "XP1") (pin "6") (pinfunction "6_6") (pintype "passive"))
    )
    (net (code "49") (name "Net-(R10-Pad1)") (class "Default")
      (node (ref "R10") (pin "1") (pinfunction "1_1") (pintype "passive"))
      (node (ref "R7") (pin "2") (pinfunction "2_2") (pintype "passive"))
      (node (ref "R9") (pin "1") (pinfunction "1_1") (pintype "passive"))
      (node (ref "X2") (pin "1") (pintype "passive"))
    )
    (net (code "50") (name "Net-(R11-Pad1)") (class "Default")
      (node (ref "R11") (pin "1") (pinfunction "1_1") (pintype "passive"))
      (node (ref "R8") (pin "1") (pinfunction "1_1") (pintype "passive"))
      (node (ref "X1") (pin "1") (pintype "passive"))
    )
    (net (code "51") (name "Net-(R21-Pad1)") (class "Default")
      (node (ref "R21") (pin "1") (pinfunction "1_1") (pintype "passive"))
      (node (ref "R22") (pin "2") (pinfunction "2_2") (pintype "passive"))
      (node (ref "X13") (pin "1") (pintype "passive"))
    )
    (net (code "52") (name "Net-(R23-Pad2)") (class "Default")
      (node (ref "R23") (pin "2") (pinfunction "2_2") (pintype "passive"))
      (node (ref "X14") (pin "1") (pintype "passive"))
    )
    (net (code "53") (name "Net-(X4-Contact0)") (class "Default")
      (node (ref "DA3") (pin "1") (pinfunction "1_1") (pintype "passive"))
      (node (ref "DA3") (pin "2") (pinfunction "2_2") (pintype "passive"))
      (node (ref "R17") (pin "1") (pinfunction "1_1") (pintype "passive"))
      (node (ref "X4") (pin "1") (pinfunction "Contact0_1") (pintype "passive"))
      (node (ref "X5") (pin "1") (pintype "passive"))
    )
    (net (code "54") (name "Net-(X8-Contact0)") (class "Default")
      (node (ref "R15") (pin "2") (pinfunction "2_2") (pintype "passive"))
      (node (ref "R16") (pin "1") (pinfunction "1_1") (pintype "passive"))
      (node (ref "X6") (pin "1") (pintype "passive"))
      (node (ref "X8") (pin "1") (pinfunction "Contact0_1") (pintype "passive"))
    )
    (net (code "55") (name "Net-(ZQ1-OSC1)") (class "Default")
      (node (ref "C3") (pin "1") (pinfunction "1_1") (pintype "passive"))
      (node (ref "R1") (pin "2") (pinfunction "2_2") (pintype "passive"))
      (node (ref "ZQ1") (pin "1") (pinfunction "OSC1_1") (pintype "passive"))
    )
    (net (code "56") (name "unconnected-(DA1-NC-Pad4)") (class "Default")
      (node (ref "DA1") (pin "4") (pinfunction "NC_4") (pintype "passive+no_connect"))
    )
    (net (code "57") (name "unconnected-(DA1-Pad4)") (class "Default")
      (node (ref "DA1") (pin "4") (pintype "passive"))
    )
    (net (code "58") (name "unconnected-(DA2-MCLK_OUT-Pad3)") (class "Default")
      (node (ref "DA2") (pin "3") (pinfunction "MCLK_OUT_3") (pintype "output"))
    )
    (net (code "59") (name "unconnected-(DD2-RA0-Pad13)") (class "Default")
      (node (ref "DD2") (pin "13") (pinfunction "RA0_13") (pintype "passive+no_connect"))
    )
    (net (code "60") (name "unconnected-(DD2-RB4-Pad33)") (class "Default")
      (node (ref "DD2") (pin "33") (pinfunction "RB4_33") (pintype "passive+no_connect"))
    )
    (net (code "61") (name "unconnected-(DD2-RB5-Pad46)") (class "Default")
      (node (ref "DD2") (pin "46") (pinfunction "RB5_46") (pintype "passive+no_connect"))
    )
    (net (code "62") (name "unconnected-(DD2-RB8-Pad43)") (class "Default")
      (node (ref "DD2") (pin "43") (pinfunction "RB8_43") (pintype "passive+no_connect"))
    )
    (net (code "63") (name "unconnected-(DD2-RC2-Pad35)") (class "Default")
      (node (ref "DD2") (pin "35") (pinfunction "RC2_35") (pintype "passive"))
    )
    (net (code "64") (name "unconnected-(DD2-RC4-Pad50)") (class "Default")
      (node (ref "DD2") (pin "50") (pinfunction "RC4_50") (pintype "passive+no_connect"))
    )
    (net (code "65") (name "unconnected-(DD2-RC5-Pad51)") (class "Default")
      (node (ref "DD2") (pin "51") (pinfunction "RC5_51") (pintype "passive+no_connect"))
    )
    (net (code "66") (name "unconnected-(DD2-RC6-Pad52)") (class "Default")
      (node (ref "DD2") (pin "52") (pinfunction "RC6_52") (pintype "passive+no_connect"))
    )
    (net (code "67") (name "unconnected-(DD2-RC7-Pad36)") (class "Default")
      (node (ref "DD2") (pin "36") (pinfunction "RC7_36") (pintype "passive+no_connect"))
    )
    (net (code "68") (name "unconnected-(DD2-RC10-Pad24)") (class "Default")
      (node (ref "DD2") (pin "24") (pinfunction "RC10_24") (pintype "passive+no_connect"))
    )
    (net (code "69") (name "unconnected-(DD2-RC14-Pad34)") (class "Default")
      (node (ref "DD2") (pin "34") (pinfunction "RC14_34") (pintype "passive+no_connect"))
    )
    (net (code "70") (name "unconnected-(DD2-RC15-Pad31)") (class "Default")
      (node (ref "DD2") (pin "31") (pinfunction "RC15_31") (pintype "passive+no_connect"))
    )
    (net (code "71") (name "unconnected-(DD2-RD0-Pad47)") (class "Default")
      (node (ref "DD2") (pin "47") (pinfunction "RD0_47") (pintype "passive+no_connect"))
    )
    (net (code "72") (name "unconnected-(DD2-RD1-Pad64)") (class "Default")
      (node (ref "DD2") (pin "64") (pinfunction "RD1_64") (pintype "passive+no_connect"))
    )
    (net (code "73") (name "unconnected-(DD2-RD2-Pad30)") (class "Default")
      (node (ref "DD2") (pin "30") (pinfunction "RD2_30") (pintype "passive+no_connect"))
    )
    (net (code "74") (name "unconnected-(DD2-RD4-Pad58)") (class "Default")
      (node (ref "DD2") (pin "58") (pinfunction "RD4_58") (pintype "passive+no_connect"))
    )
    (net (code "75") (name "unconnected-(DD2-RD5-Pad53)") (class "Default")
      (node (ref "DD2") (pin "53") (pinfunction "RD5_53") (pintype "passive+no_connect"))
    )
    (net (code "76") (name "unconnected-(DD2-RD7-Pad21)") (class "Default")
      (node (ref "DD2") (pin "21") (pinfunction "RD7_21") (pintype "passive+no_connect"))
    )
    (net (code "77") (name "unconnected-(DD2-RD8-Pad42)") (class "Default")
      (node (ref "DD2") (pin "42") (pinfunction "RD8_42") (pintype "passive+no_connect"))
    )
    (net (code "78") (name "unconnected-(DD2-RD9-Pad40)") (class "Default")
      (node (ref "DD2") (pin "40") (pinfunction "RD9_40") (pintype "passive+no_connect"))
    )
    (net (code "79") (name "unconnected-(DD2-RD10-Pad6)") (class "Default")
      (node (ref "DD2") (pin "6") (pinfunction "RD10_6") (pintype "passive+no_connect"))
    )
    (net (code "80") (name "unconnected-(DD2-RD11-Pad45)") (class "Default")
      (node (ref "DD2") (pin "45") (pinfunction "RD11_45") (pintype "passive+no_connect"))
    )
    (net (code "81") (name "unconnected-(DD2-RD12-Pad8)") (class "Default")
      (node (ref "DD2") (pin "8") (pinfunction "RD12_8") (pintype "passive+no_connect"))
    )
    (net (code "82") (name "unconnected-(DD2-RD13-Pad22)") (class "Default")
      (node (ref "DD2") (pin "22") (pinfunction "RD13_22") (pintype "passive+no_connect"))
    )
    (net (code "83") (name "unconnected-(DD2-RD14-Pad39)") (class "Default")
      (node (ref "DD2") (pin "39") (pinfunction "RD14_39") (pintype "passive+no_connect"))
    )
    (net (code "84") (name "unconnected-(DD2-RD15-Pad59)") (class "Default")
      (node (ref "DD2") (pin "59") (pinfunction "RD15_59") (pintype "passive+no_connect"))
    )
    (net (code "85") (name "unconnected-(XP1-Pad2)") (class "Default")
      (node (ref "XP1") (pin "2") (pinfunction "2_2") (pintype "passive+no_connect"))
    )
    (net (code "86") (name "unconnected-(XP1-Pad4)") (class "Default")
      (node (ref "XP1") (pin "4") (pinfunction "4_4") (pintype "passive+no_connect"))
    )
    (net (code "87") (name "unconnected-(XP1-Pad9)") (class "Default")
      (node (ref "XP1") (pin "9") (pinfunction "9_9") (pintype "passive+no_connect"))
    )
    (net (code "88") (name "unconnected-(XP1-Pad13)") (class "Default")
      (node (ref "XP1") (pin "13") (pinfunction "13_13") (pintype "passive+no_connect"))
    )
  )
)
